# 5_main_radio.net
KiCad netlist of a schematic drawn in Altium Designer
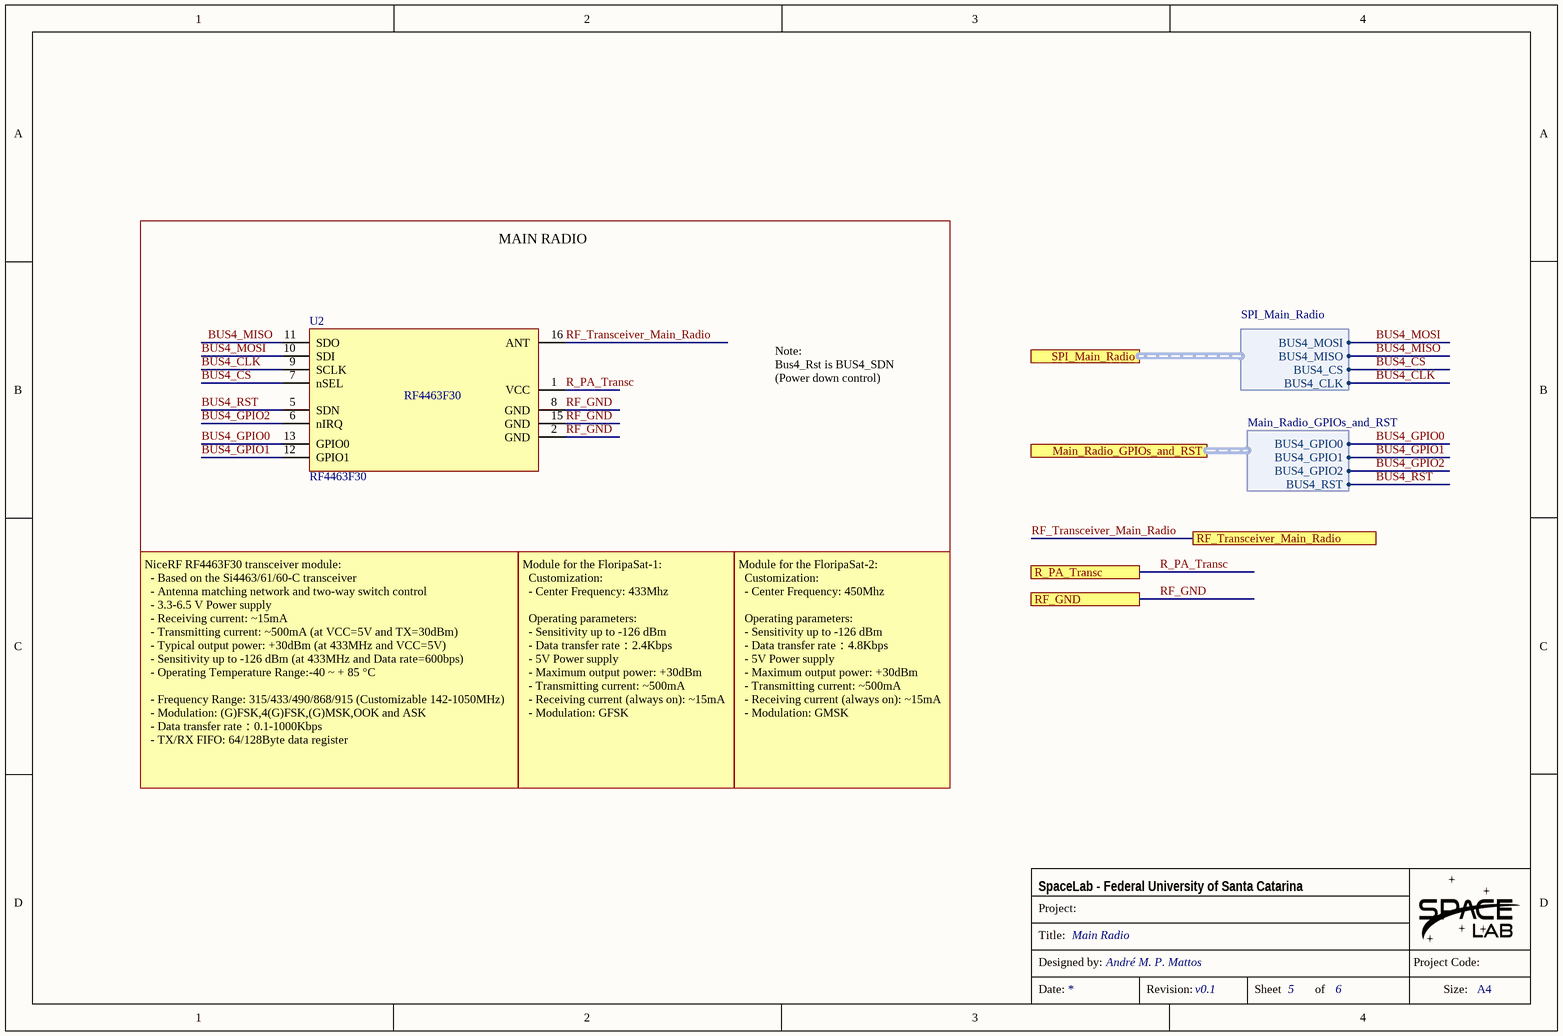
[diagram p0: 5_main_radio.schdoc]

(export (version "E")
  (design (tool "Eeschema 10.0.6"))
  (components
    (comp (ref "U2")
      (value "RF4463F30")
      (footprint "RF4463F30")
      (description "RF4463F30 High Power Wireless Transceiver Module")
      (libsource (lib "FloripaSatSchlib") (part "RF4463F30"))
    )
  )
  (nets
    (net (code "3") (name "/BUS4_CLK") (class "Default")
      (node (ref "U2") (pin "9") (pinfunction "SCLK_9") (pintype "passive"))
    )
    (net (code "4") (name "/BUS4_CS") (class "Default")
      (node (ref "U2") (pin "7") (pinfunction "nSEL_7") (pintype "passive"))
    )
    (net (code "5") (name "/BUS4_GPIO0") (class "Default")
      (node (ref "U2") (pin "13") (pinfunction "GPIO0_13") (pintype "passive"))
    )
    (net (code "6") (name "/BUS4_GPIO1") (class "Default")
      (node (ref "U2") (pin "12") (pinfunction "GPIO1_12") (pintype "passive"))
    )
    (net (code "7") (name "/BUS4_GPIO2") (class "Default")
      (node (ref "U2") (pin "6") (pinfunction "nIRQ_6") (pintype "passive"))
    )
    (net (code "8") (name "/BUS4_MISO") (class "Default")
      (node (ref "U2") (pin "11") (pinfunction "SDO_11") (pintype "passive"))
    )
    (net (code "9") (name "/BUS4_MOSI") (class "Default")
      (node (ref "U2") (pin "10") (pinfunction "SDI_10") (pintype "passive"))
    )
    (net (code "10") (name "/BUS4_RST") (class "Default")
      (node (ref "U2") (pin "5") (pinfunction "SDN_5") (pintype "passive"))
    )
    (net (code "11") (name "/RF_GND") (class "Default")
      (node (ref "U2") (pin "15") (pinfunction "GND_15") (pintype "passive"))
      (node (ref "U2") (pin "2") (pinfunction "GND_2") (pintype "passive"))
      (node (ref "U2") (pin "8") (pinfunction "GND_8") (pintype "passive"))
    )
    (net (code "12") (name "/RF_Transceiver_Main_Radio") (class "Default")
      (node (ref "U2") (pin "16") (pinfunction "ANT_16") (pintype "passive"))
    )
    (net (code "13") (name "/R_PA_Transc") (class "Default")
      (node (ref "U2") (pin "1") (pinfunction "VCC_1") (pintype "passive"))
    )
  )
)
